# PHONO_PREAMP.net
KiCad netlist of a schematic drawn in Altium Designer
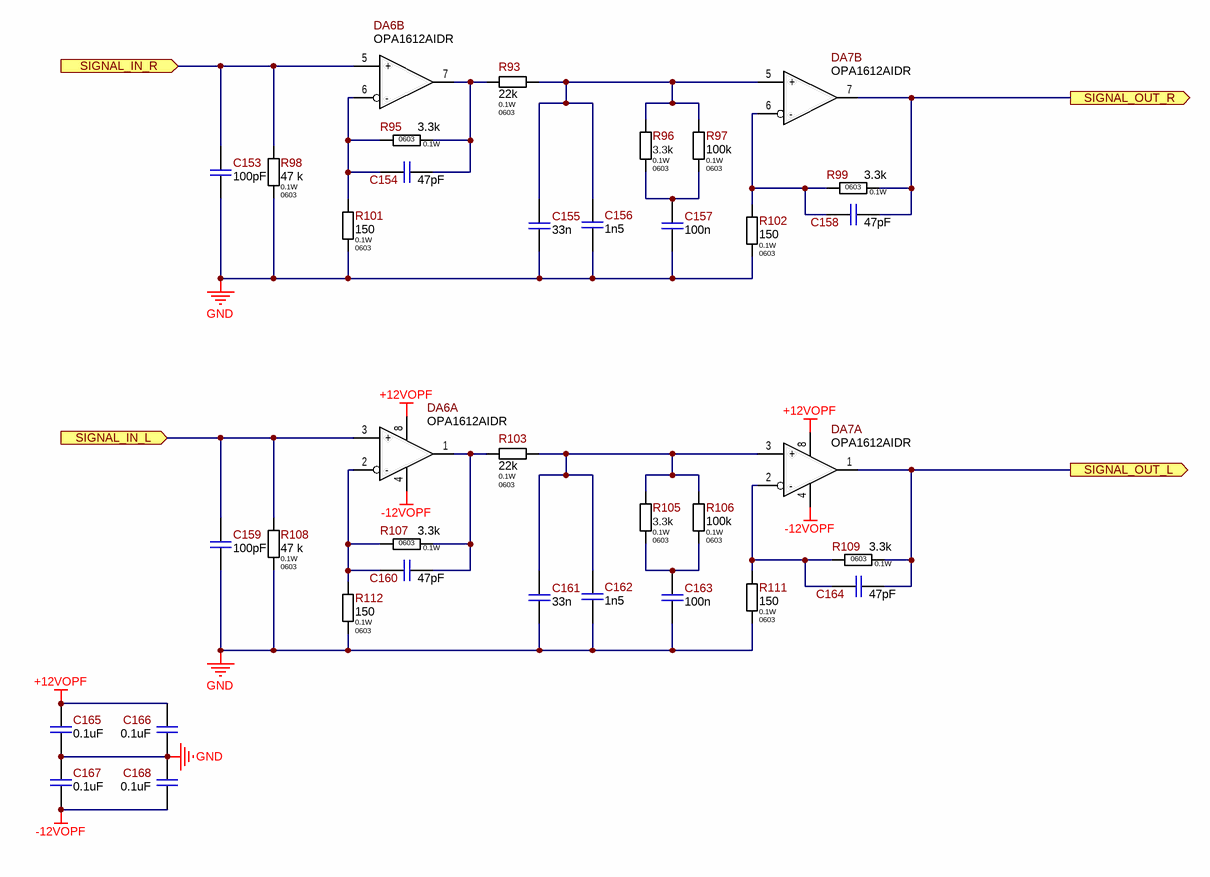
[diagram p0: PHONO_PREAMP.SchDoc]

(export (version "E")
  (design (tool "Eeschema 10.0.6"))
  (components
    (comp (ref "C153")
      (value "100pF")
      (footprint "C0603(1608)")
      (description "CAP CER n1F 50V X7R 0603")
      (fields (field (name "PART NUMBER") "100pF  50V C0603") (field (name "TOLERANCE") "±20%"))
      (libsource (lib "Database") (part "Capacitor_Ceramic"))
    )
    (comp (ref "C154")
      (value "47pF")
      (footprint "C0603(1608)")
      (description "CAP CER n1F 50V X7R 0603")
      (fields (field (name "PART NUMBER") "100pF  50V C0603") (field (name "TOLERANCE") "±20%"))
      (libsource (lib "Database") (part "Capacitor_Ceramic"))
    )
    (comp (ref "C155")
      (value "33n")
      (footprint "WIMA_2,5x6,5x7,2")
      (description "WIMA 33NF, 40VAC, 63VDC: 5mm, ± 10%")
      (fields (field (name "PART NUMBER") "33n  AC40V DC63V 2,5x6,5x7,2") (field (name "TOLERANCE") "10%"))
      (libsource (lib "Database") (part "Capacitor_Ceramic"))
    )
    (comp (ref "C156")
      (value "1n5")
      (footprint "C0603(1608)")
      (description "CAP CER n1F 50V X7R 0603")
      (fields (field (name "PART NUMBER") "100pF  50V C0603") (field (name "TOLERANCE") "±20%"))
      (libsource (lib "Database") (part "Capacitor_Ceramic"))
    )
    (comp (ref "C157")
      (value "100n")
      (footprint "WIMA_2,5x6,5x7,2")
      (description "WIMA 100NF, 40VAC, 63VDC: 5mm, ± 10%")
      (fields (field (name "PART NUMBER") "100n  AC40V DC63V 2,5x6,5x7,2") (field (name "TOLERANCE") "10%"))
      (libsource (lib "Database") (part "Capacitor_Ceramic"))
    )
    (comp (ref "C158")
      (value "47pF")
      (footprint "C0603(1608)")
      (description "CAP CER n1F 50V X7R 0603")
      (fields (field (name "PART NUMBER") "100pF  50V C0603") (field (name "TOLERANCE") "±20%"))
      (libsource (lib "Database") (part "Capacitor_Ceramic"))
    )
    (comp (ref "C159")
      (value "100pF")
      (footprint "C0603(1608)")
      (description "CAP CER n1F 50V X7R 0603")
      (fields (field (name "PART NUMBER") "100pF  50V C0603") (field (name "TOLERANCE") "±20%"))
      (libsource (lib "Database") (part "Capacitor_Ceramic"))
    )
    (comp (ref "C160")
      (value "47pF")
      (footprint "C0603(1608)")
      (description "CAP CER n1F 50V X7R 0603")
      (fields (field (name "PART NUMBER") "100pF  50V C0603") (field (name "TOLERANCE") "±20%"))
      (libsource (lib "Database") (part "Capacitor_Ceramic"))
    )
    (comp (ref "C161")
      (value "33n")
      (footprint "WIMA_2,5x6,5x7,2")
      (description "WIMA 33NF, 40VAC, 63VDC: 5mm, ± 10%")
      (fields (field (name "PART NUMBER") "33n  AC40V DC63V 2,5x6,5x7,2") (field (name "TOLERANCE") "10%"))
      (libsource (lib "Database") (part "Capacitor_Ceramic"))
    )
    (comp (ref "C162")
      (value "1n5")
      (footprint "C0603(1608)")
      (description "CAP CER n1F 50V X7R 0603")
      (fields (field (name "PART NUMBER") "100pF  50V C0603") (field (name "TOLERANCE") "±20%"))
      (libsource (lib "Database") (part "Capacitor_Ceramic"))
    )
    (comp (ref "C163")
      (value "100n")
      (footprint "WIMA_2,5x6,5x7,2")
      (description "WIMA 100NF, 40VAC, 63VDC: 5mm, ± 10%")
      (fields (field (name "PART NUMBER") "100n  AC40V DC63V 2,5x6,5x7,2") (field (name "TOLERANCE") "10%"))
      (libsource (lib "Database") (part "Capacitor_Ceramic"))
    )
    (comp (ref "C164")
      (value "47pF")
      (footprint "C0603(1608)")
      (description "CAP CER n1F 50V X7R 0603")
      (fields (field (name "PART NUMBER") "100pF  50V C0603") (field (name "TOLERANCE") "±20%"))
      (libsource (lib "Database") (part "Capacitor_Ceramic"))
    )
    (comp (ref "C165")
      (value "0.1uF")
      (footprint "C0603(1608)")
      (description "CAP CER 0.1UF 50V X7R 0603")
      (fields (field (name "PART NUMBER") "0.1uF  50V C0603") (field (name "TOLERANCE") "±10%"))
      (libsource (lib "Database") (part "Capacitor_Ceramic"))
    )
    (comp (ref "C166")
      (value "0.1uF")
      (footprint "C0603(1608)")
      (description "CAP CER 0.1UF 50V X7R 0603")
      (fields (field (name "PART NUMBER") "0.1uF  50V C0603") (field (name "TOLERANCE") "±10%"))
      (libsource (lib "Database") (part "Capacitor_Ceramic"))
    )
    (comp (ref "C167")
      (value "0.1uF")
      (footprint "C0603(1608)")
      (description "CAP CER 0.1UF 50V X7R 0603")
      (fields (field (name "PART NUMBER") "0.1uF  50V C0603") (field (name "TOLERANCE") "±10%"))
      (libsource (lib "Database") (part "Capacitor_Ceramic"))
    )
    (comp (ref "C168")
      (value "0.1uF")
      (footprint "C0603(1608)")
      (description "CAP CER 0.1UF 50V X7R 0603")
      (fields (field (name "PART NUMBER") "0.1uF  50V C0603") (field (name "TOLERANCE") "±10%"))
      (libsource (lib "Database") (part "Capacitor_Ceramic"))
    )
    (comp (ref "DA6")
      (value "OPA1612AIDR")
      (footprint "SOIC8")
      (description "Audio Amplifier 2 Circuit Rail-to-Rail 8-SOIC")
      (fields (field (name "MANUFACTURER") "Texas Instruments"))
      (libsource (lib "Database") (part "AMP8"))
    )
    (comp (ref "DA7")
      (value "OPA1612AIDR")
      (footprint "SOIC8")
      (description "Audio Amplifier 2 Circuit Rail-to-Rail 8-SOIC")
      (fields (field (name "MANUFACTURER") "Texas Instruments"))
      (libsource (lib "Database") (part "AMP8"))
    )
    (comp (ref "R93")
      (value "22k")
      (footprint "R0603")
      (description "RES SMD 750 OHM  ±1% 1/10W 0603")
      (fields
        (field (name "POWER RATING") "0.1W")
        (field (name "PACKAGE/CASE") "0603")
        (field (name "PART NUMBER") "750  R0603")
        (field (name "TOLERANCE") "±1%")
      )
      (libsource (lib "Database") (part "R0603"))
    )
    (comp (ref "R95")
      (value "3.3k")
      (footprint "R0603")
      (description "RES SMD 100 k OHM  ±1% 1/10W 0603")
      (fields
        (field (name "POWER RATING") "0.1W")
        (field (name "PACKAGE/CASE") "0603")
        (field (name "PART NUMBER") "100 k  R0603")
        (field (name "TOLERANCE") "±1%")
      )
      (libsource (lib "Database") (part "R0603"))
    )
    (comp (ref "R96")
      (value "3.3k")
      (footprint "R0603")
      (description "RES SMD 100 k OHM  ±1% 1/10W 0603")
      (fields
        (field (name "POWER RATING") "0.1W")
        (field (name "PACKAGE/CASE") "0603")
        (field (name "PART NUMBER") "100 k  R0603")
        (field (name "TOLERANCE") "±1%")
      )
      (libsource (lib "Database") (part "R0603"))
    )
    (comp (ref "R97")
      (value "100k")
      (footprint "R0603")
      (description "RES SMD 750 OHM  ±1% 1/10W 0603")
      (fields
        (field (name "POWER RATING") "0.1W")
        (field (name "PACKAGE/CASE") "0603")
        (field (name "PART NUMBER") "750  R0603")
        (field (name "TOLERANCE") "±1%")
      )
      (libsource (lib "Database") (part "R0603"))
    )
    (comp (ref "R98")
      (value "47 k")
      (footprint "R0603")
      (description "RES SMD 47 k OHM  ±1% 1/10W 0603")
      (fields
        (field (name "POWER RATING") "0.1W")
        (field (name "PACKAGE/CASE") "0603")
        (field (name "PART NUMBER") "47 k  R0603")
        (field (name "TOLERANCE") "±1%")
      )
      (libsource (lib "Database") (part "R0603"))
    )
    (comp (ref "R99")
      (value "3.3k")
      (footprint "R0603")
      (description "RES SMD 100 k OHM  ±1% 1/10W 0603")
      (fields
        (field (name "POWER RATING") "0.1W")
        (field (name "PACKAGE/CASE") "0603")
        (field (name "PART NUMBER") "100 k  R0603")
        (field (name "TOLERANCE") "±1%")
      )
      (libsource (lib "Database") (part "R0603"))
    )
    (comp (ref "R101")
      (value "150")
      (footprint "R0603")
      (description "RES SMD 4.7 k OHM  ±1% 1/10W 0603")
      (fields
        (field (name "POWER RATING") "0.1W")
        (field (name "PACKAGE/CASE") "0603")
        (field (name "PART NUMBER") "4.7 k  R0603")
        (field (name "TOLERANCE") "±1%")
      )
      (libsource (lib "Database") (part "R0603"))
    )
    (comp (ref "R102")
      (value "150")
      (footprint "R0603")
      (description "RES SMD 4.7 k OHM  ±1% 1/10W 0603")
      (fields
        (field (name "POWER RATING") "0.1W")
        (field (name "PACKAGE/CASE") "0603")
        (field (name "PART NUMBER") "4.7 k  R0603")
        (field (name "TOLERANCE") "±1%")
      )
      (libsource (lib "Database") (part "R0603"))
    )
    (comp (ref "R103")
      (value "22k")
      (footprint "R0603")
      (description "RES SMD 750 OHM  ±1% 1/10W 0603")
      (fields
        (field (name "POWER RATING") "0.1W")
        (field (name "PACKAGE/CASE") "0603")
        (field (name "PART NUMBER") "750  R0603")
        (field (name "TOLERANCE") "±1%")
      )
      (libsource (lib "Database") (part "R0603"))
    )
    (comp (ref "R105")
      (value "3.3k")
      (footprint "R0603")
      (description "RES SMD 100 k OHM  ±1% 1/10W 0603")
      (fields
        (field (name "POWER RATING") "0.1W")
        (field (name "PACKAGE/CASE") "0603")
        (field (name "PART NUMBER") "100 k  R0603")
        (field (name "TOLERANCE") "±1%")
      )
      (libsource (lib "Database") (part "R0603"))
    )
    (comp (ref "R106")
      (value "100k")
      (footprint "R0603")
      (description "RES SMD 750 OHM  ±1% 1/10W 0603")
      (fields
        (field (name "POWER RATING") "0.1W")
        (field (name "PACKAGE/CASE") "0603")
        (field (name "PART NUMBER") "750  R0603")
        (field (name "TOLERANCE") "±1%")
      )
      (libsource (lib "Database") (part "R0603"))
    )
    (comp (ref "R107")
      (value "3.3k")
      (footprint "R0603")
      (description "RES SMD 100 k OHM  ±1% 1/10W 0603")
      (fields
        (field (name "POWER RATING") "0.1W")
        (field (name "PACKAGE/CASE") "0603")
        (field (name "PART NUMBER") "100 k  R0603")
        (field (name "TOLERANCE") "±1%")
      )
      (libsource (lib "Database") (part "R0603"))
    )
    (comp (ref "R108")
      (value "47 k")
      (footprint "R0603")
      (description "RES SMD 47 k OHM  ±1% 1/10W 0603")
      (fields
        (field (name "POWER RATING") "0.1W")
        (field (name "PACKAGE/CASE") "0603")
        (field (name "PART NUMBER") "47 k  R0603")
        (field (name "TOLERANCE") "±1%")
      )
      (libsource (lib "Database") (part "R0603"))
    )
    (comp (ref "R109")
      (value "3.3k")
      (footprint "R0603")
      (description "RES SMD 100 k OHM  ±1% 1/10W 0603")
      (fields
        (field (name "POWER RATING") "0.1W")
        (field (name "PACKAGE/CASE") "0603")
        (field (name "PART NUMBER") "100 k  R0603")
        (field (name "TOLERANCE") "±1%")
      )
      (libsource (lib "Database") (part "R0603"))
    )
    (comp (ref "R111")
      (value "150")
      (footprint "R0603")
      (description "RES SMD 4.7 k OHM  ±1% 1/10W 0603")
      (fields
        (field (name "POWER RATING") "0.1W")
        (field (name "PACKAGE/CASE") "0603")
        (field (name "PART NUMBER") "4.7 k  R0603")
        (field (name "TOLERANCE") "±1%")
      )
      (libsource (lib "Database") (part "R0603"))
    )
    (comp (ref "R112")
      (value "150")
      (footprint "R0603")
      (description "RES SMD 4.7 k OHM  ±1% 1/10W 0603")
      (fields
        (field (name "POWER RATING") "0.1W")
        (field (name "PACKAGE/CASE") "0603")
        (field (name "PART NUMBER") "4.7 k  R0603")
        (field (name "TOLERANCE") "±1%")
      )
      (libsource (lib "Database") (part "R0603"))
    )
  )
  (nets
    (net (code "1") (name "+12VOPF") (class "Default")
      (node (ref "C165") (pin "1") (pinfunction "1_1") (pintype "passive"))
      (node (ref "C166") (pin "1") (pinfunction "1_1") (pintype "passive"))
      (node (ref "DA6") (pin "8") (pinfunction "V+_8") (pintype "passive"))
      (node (ref "DA7") (pin "8") (pinfunction "V+_8") (pintype "passive"))
    )
    (net (code "2") (name "-12VOPF") (class "Default")
      (node (ref "C167") (pin "2") (pinfunction "2_2") (pintype "passive"))
      (node (ref "C168") (pin "2") (pinfunction "2_2") (pintype "passive"))
      (node (ref "DA6") (pin "4") (pinfunction "V-_4") (pintype "passive"))
      (node (ref "DA7") (pin "4") (pinfunction "V-_4") (pintype "passive"))
    )
    (net (code "3") (name "/SIGNAL_IN_L") (class "Default")
      (node (ref "C159") (pin "2") (pinfunction "2_2") (pintype "passive"))
      (node (ref "DA6") (pin "3") (pinfunction "+_3") (pintype "passive"))
      (node (ref "R108") (pin "2") (pinfunction "2_2") (pintype "passive"))
    )
    (net (code "4") (name "/SIGNAL_IN_R") (class "Default")
      (node (ref "C153") (pin "2") (pinfunction "2_2") (pintype "passive"))
      (node (ref "DA6") (pin "5") (pinfunction "+_5") (pintype "passive"))
      (node (ref "R98") (pin "2") (pinfunction "2_2") (pintype "passive"))
    )
    (net (code "5") (name "/SIGNAL_OUT_L") (class "Default")
      (node (ref "C164") (pin "1") (pinfunction "1_1") (pintype "passive"))
      (node (ref "DA7") (pin "1") (pinfunction "Out_1") (pintype "passive"))
      (node (ref "R109") (pin "2") (pinfunction "2_2") (pintype "passive"))
    )
    (net (code "6") (name "/SIGNAL_OUT_R") (class "Default")
      (node (ref "C158") (pin "1") (pinfunction "1_1") (pintype "passive"))
      (node (ref "DA7") (pin "7") (pinfunction "Out_7") (pintype "passive"))
      (node (ref "R99") (pin "2") (pinfunction "2_2") (pintype "passive"))
    )
    (net (code "7") (name "GND") (class "Default")
      (node (ref "C153") (pin "1") (pinfunction "1_1") (pintype "passive"))
      (node (ref "C155") (pin "1") (pinfunction "1_1") (pintype "passive"))
      (node (ref "C156") (pin "2") (pinfunction "2_2") (pintype "passive"))
      (node (ref "C157") (pin "1") (pinfunction "1_1") (pintype "passive"))
      (node (ref "C159") (pin "1") (pinfunction "1_1") (pintype "passive"))
      (node (ref "C161") (pin "1") (pinfunction "1_1") (pintype "passive"))
      (node (ref "C162") (pin "2") (pinfunction "2_2") (pintype "passive"))
      (node (ref "C163") (pin "1") (pinfunction "1_1") (pintype "passive"))
      (node (ref "C165") (pin "2") (pinfunction "2_2") (pintype "passive"))
      (node (ref "C166") (pin "2") (pinfunction "2_2") (pintype "passive"))
      (node (ref "C167") (pin "1") (pinfunction "1_1") (pintype "passive"))
      (node (ref "C168") (pin "1") (pinfunction "1_1") (pintype "passive"))
      (node (ref "R101") (pin "1") (pinfunction "1_1") (pintype "passive"))
      (node (ref "R102") (pin "1") (pinfunction "1_1") (pintype "passive"))
      (node (ref "R108") (pin "1") (pinfunction "1_1") (pintype "passive"))
      (node (ref "R111") (pin "1") (pinfunction "1_1") (pintype "passive"))
      (node (ref "R112") (pin "1") (pinfunction "1_1") (pintype "passive"))
      (node (ref "R98") (pin "1") (pinfunction "1_1") (pintype "passive"))
    )
    (net (code "8") (name "Net-(C157-Pad2)") (class "Default")
      (node (ref "C157") (pin "2") (pinfunction "2_2") (pintype "passive"))
      (node (ref "R96") (pin "1") (pinfunction "1_1") (pintype "passive"))
      (node (ref "R97") (pin "1") (pinfunction "1_1") (pintype "passive"))
    )
    (net (code "9") (name "Net-(C163-Pad2)") (class "Default")
      (node (ref "C163") (pin "2") (pinfunction "2_2") (pintype "passive"))
      (node (ref "R105") (pin "1") (pinfunction "1_1") (pintype "passive"))
      (node (ref "R106") (pin "1") (pinfunction "1_1") (pintype "passive"))
    )
    (net (code "10") (name "Net-(DA6A--)") (class "Default")
      (node (ref "C160") (pin "2") (pinfunction "2_2") (pintype "passive"))
      (node (ref "DA6") (pin "2") (pinfunction "-_2") (pintype "passive"))
      (node (ref "R107") (pin "1") (pinfunction "1_1") (pintype "passive"))
      (node (ref "R112") (pin "2") (pinfunction "2_2") (pintype "passive"))
    )
    (net (code "11") (name "Net-(DA6A-Out)") (class "Default")
      (node (ref "C160") (pin "1") (pinfunction "1_1") (pintype "passive"))
      (node (ref "DA6") (pin "1") (pinfunction "Out_1") (pintype "passive"))
      (node (ref "R103") (pin "1") (pinfunction "1_1") (pintype "passive"))
      (node (ref "R107") (pin "2") (pinfunction "2_2") (pintype "passive"))
    )
    (net (code "12") (name "Net-(DA6B--)") (class "Default")
      (node (ref "C154") (pin "2") (pinfunction "2_2") (pintype "passive"))
      (node (ref "DA6") (pin "6") (pinfunction "-_6") (pintype "passive"))
      (node (ref "R101") (pin "2") (pinfunction "2_2") (pintype "passive"))
      (node (ref "R95") (pin "1") (pinfunction "1_1") (pintype "passive"))
    )
    (net (code "13") (name "Net-(DA6B-Out)") (class "Default")
      (node (ref "C154") (pin "1") (pinfunction "1_1") (pintype "passive"))
      (node (ref "DA6") (pin "7") (pinfunction "Out_7") (pintype "passive"))
      (node (ref "R93") (pin "1") (pinfunction "1_1") (pintype "passive"))
      (node (ref "R95") (pin "2") (pinfunction "2_2") (pintype "passive"))
    )
    (net (code "14") (name "Net-(DA7A-+)") (class "Default")
      (node (ref "C161") (pin "2") (pinfunction "2_2") (pintype "passive"))
      (node (ref "C162") (pin "1") (pinfunction "1_1") (pintype "passive"))
      (node (ref "DA7") (pin "3") (pinfunction "+_3") (pintype "passive"))
      (node (ref "R103") (pin "2") (pinfunction "2_2") (pintype "passive"))
      (node (ref "R105") (pin "2") (pinfunction "2_2") (pintype "passive"))
      (node (ref "R106") (pin "2") (pinfunction "2_2") (pintype "passive"))
    )
    (net (code "15") (name "Net-(DA7A--)") (class "Default")
      (node (ref "C164") (pin "2") (pinfunction "2_2") (pintype "passive"))
      (node (ref "DA7") (pin "2") (pinfunction "-_2") (pintype "passive"))
      (node (ref "R109") (pin "1") (pinfunction "1_1") (pintype "passive"))
      (node (ref "R111") (pin "2") (pinfunction "2_2") (pintype "passive"))
    )
    (net (code "16") (name "Net-(DA7B-+)") (class "Default")
      (node (ref "C155") (pin "2") (pinfunction "2_2") (pintype "passive"))
      (node (ref "C156") (pin "1") (pinfunction "1_1") (pintype "passive"))
      (node (ref "DA7") (pin "5") (pinfunction "+_5") (pintype "passive"))
      (node (ref "R93") (pin "2") (pinfunction "2_2") (pintype "passive"))
      (node (ref "R96") (pin "2") (pinfunction "2_2") (pintype "passive"))
      (node (ref "R97") (pin "2") (pinfunction "2_2") (pintype "passive"))
    )
    (net (code "17") (name "Net-(DA7B--)") (class "Default")
      (node (ref "C158") (pin "2") (pinfunction "2_2") (pintype "passive"))
      (node (ref "DA7") (pin "6") (pinfunction "-_6") (pintype "passive"))
      (node (ref "R102") (pin "2") (pinfunction "2_2") (pintype "passive"))
      (node (ref "R99") (pin "1") (pinfunction "1_1") (pintype "passive"))
    )
  )
)
